# EEG1CH.net
KiCad netlist of a schematic drawn in EAGLE
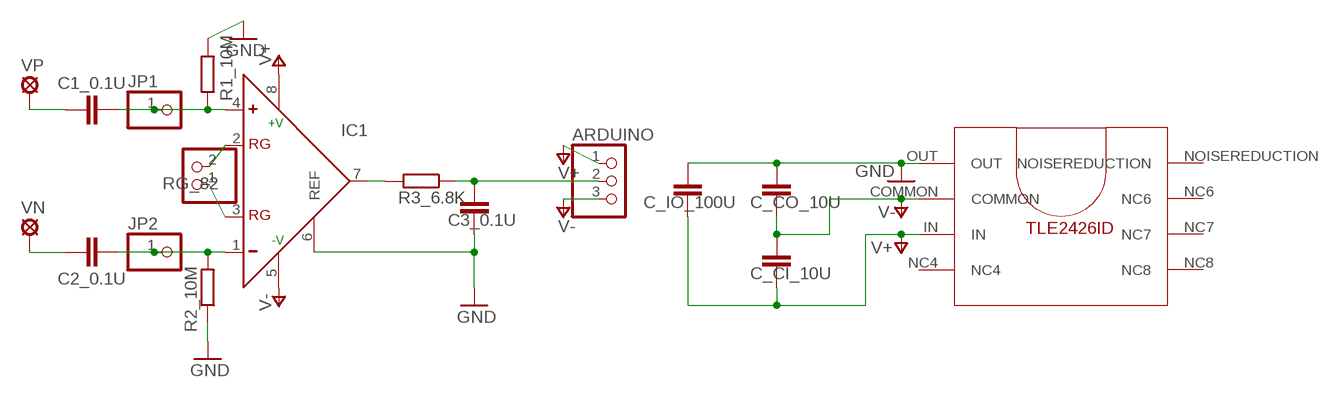
[diagram p0: schematic, sheet 1]

(export (version "E")
  (design (tool "Eeschema 10.0.6"))
  (components
    (comp (ref "ARDUINO")
      (value "PINHD-1X3")
      (footprint "eagle-import:1X03")
      (libsource (lib "eagle-import") (part "PINHD-1X3"))
    )
    (comp (ref "C1_0.1U")
      (value "C2,5-3")
      (footprint "eagle-import:C2.5-3")
      (libsource (lib "eagle-import") (part "C2,5-3"))
    )
    (comp (ref "C2_0.1U")
      (value "C2,5-3")
      (footprint "eagle-import:C2.5-3")
      (libsource (lib "eagle-import") (part "C2,5-3"))
    )
    (comp (ref "C3_0.1U")
      (value "C2,5-3")
      (footprint "eagle-import:C2.5-3")
      (libsource (lib "eagle-import") (part "C2,5-3"))
    )
    (comp (ref "C_CI_10U")
      (value "C2,5-3")
      (footprint "eagle-import:C2.5-3")
      (libsource (lib "eagle-import") (part "C2,5-3"))
    )
    (comp (ref "C_CO_10U")
      (value "C2,5-3")
      (footprint "eagle-import:C2.5-3")
      (libsource (lib "eagle-import") (part "C2,5-3"))
    )
    (comp (ref "C_IO_100U")
      (value "C2,5-3")
      (footprint "eagle-import:C2.5-3")
      (libsource (lib "eagle-import") (part "C2,5-3"))
    )
    (comp (ref "IC1")
      (value "AD8227")
      (footprint "eagle-import:SO8")
      (libsource (lib "eagle-import") (part "AD8227"))
    )
    (comp (ref "JP1")
      (value "PINHD-1X1")
      (footprint "eagle-import:1X01")
      (libsource (lib "eagle-import") (part "PINHD-1X1"))
    )
    (comp (ref "JP2")
      (value "PINHD-1X1")
      (footprint "eagle-import:1X01")
      (libsource (lib "eagle-import") (part "PINHD-1X1"))
    )
    (comp (ref "R1_10M")
      (value "R-EU_R2012")
      (footprint "eagle-import:R2012")
      (libsource (lib "eagle-import") (part "R-EU_R2012"))
    )
    (comp (ref "R2_10M")
      (value "R-EU_R2012")
      (footprint "eagle-import:R2012")
      (libsource (lib "eagle-import") (part "R-EU_R2012"))
    )
    (comp (ref "R3_6.8K")
      (value "R-EU_R2012")
      (footprint "eagle-import:R2012")
      (libsource (lib "eagle-import") (part "R-EU_R2012"))
    )
    (comp (ref "RG_82")
      (value "PINHD-1X2")
      (footprint "eagle-import:1X02")
      (libsource (lib "eagle-import") (part "PINHD-1X2"))
    )
    (comp (ref "U$1")
      (value "TLE2426ID")
      (footprint "eagle-import:TLE2426ID")
      (libsource (lib "eagle-import") (part "TLE2426ID"))
    )
    (comp (ref "VN")
      (value "SE13")
      (footprint "eagle-import:SE13")
      (libsource (lib "eagle-import") (part "SE13"))
    )
    (comp (ref "VP")
      (value "SE13")
      (footprint "eagle-import:SE13")
      (libsource (lib "eagle-import") (part "SE13"))
    )
  )
  (nets
    (net (code "1") (name "GND") (class "Default")
      (node (ref "C3_0.1U") (pin "2") (pinfunction "2_2") (pintype "passive"))
      (node (ref "C_CO_10U") (pin "1") (pinfunction "1_1") (pintype "passive"))
      (node (ref "C_IO_100U") (pin "1") (pinfunction "1_1") (pintype "passive"))
      (node (ref "IC1") (pin "6") (pinfunction "REF_6") (pintype "passive"))
      (node (ref "R1_10M") (pin "2") (pinfunction "2_2") (pintype "passive"))
      (node (ref "R2_10M") (pin "1") (pinfunction "1_1") (pintype "passive"))
      (node (ref "U$1") (pin "OUT") (pinfunction "OUT_OUT") (pintype "bidirectional"))
    )
    (net (code "2") (name "Net-(ARDUINO-Pad2)") (class "Default")
      (node (ref "ARDUINO") (pin "2") (pinfunction "2_2") (pintype "passive"))
      (node (ref "C3_0.1U") (pin "1") (pinfunction "1_1") (pintype "passive"))
      (node (ref "R3_6.8K") (pin "1") (pinfunction "1_1") (pintype "passive"))
    )
    (net (code "3") (name "Net-(C1_0.1U-Pad1)") (class "Default")
      (node (ref "C1_0.1U") (pin "1") (pinfunction "1_1") (pintype "passive"))
      (node (ref "VP") (pin "MP") (pinfunction "MP_MP") (pintype "passive"))
    )
    (net (code "4") (name "Net-(C2_0.1U-Pad1)") (class "Default")
      (node (ref "C2_0.1U") (pin "1") (pinfunction "1_1") (pintype "passive"))
      (node (ref "VN") (pin "MP") (pinfunction "MP_MP") (pintype "passive"))
    )
    (net (code "5") (name "Net-(IC1-+)") (class "Default")
      (node (ref "C1_0.1U") (pin "2") (pinfunction "2_2") (pintype "passive"))
      (node (ref "IC1") (pin "4") (pinfunction "+_4") (pintype "input"))
      (node (ref "JP1") (pin "1") (pinfunction "1_1") (pintype "passive"))
      (node (ref "R1_10M") (pin "1") (pinfunction "1_1") (pintype "passive"))
    )
    (net (code "6") (name "Net-(IC1--)") (class "Default")
      (node (ref "C2_0.1U") (pin "2") (pinfunction "2_2") (pintype "passive"))
      (node (ref "IC1") (pin "1") (pinfunction "-_1") (pintype "input"))
      (node (ref "JP2") (pin "1") (pinfunction "1_1") (pintype "passive"))
      (node (ref "R2_10M") (pin "2") (pinfunction "2_2") (pintype "passive"))
    )
    (net (code "7") (name "Net-(IC1-OUT)") (class "Default")
      (node (ref "IC1") (pin "7") (pinfunction "OUT_7") (pintype "output"))
      (node (ref "R3_6.8K") (pin "2") (pinfunction "2_2") (pintype "passive"))
    )
    (net (code "8") (name "Net-(IC1-RG-Pad2)") (class "Default")
      (node (ref "IC1") (pin "2") (pinfunction "RG_2") (pintype "passive"))
      (node (ref "RG_82") (pin "2") (pinfunction "2_2") (pintype "passive"))
    )
    (net (code "9") (name "Net-(IC1-RG-Pad3)") (class "Default")
      (node (ref "IC1") (pin "3") (pinfunction "RG_3") (pintype "passive"))
      (node (ref "RG_82") (pin "1") (pinfunction "1_1") (pintype "passive"))
    )
    (net (code "10") (name "V+") (class "Default")
      (node (ref "ARDUINO") (pin "1") (pinfunction "1_1") (pintype "passive"))
      (node (ref "C_CI_10U") (pin "2") (pinfunction "2_2") (pintype "passive"))
      (node (ref "C_IO_100U") (pin "2") (pinfunction "2_2") (pintype "passive"))
      (node (ref "IC1") (pin "8") (pinfunction "+V_8") (pintype "power_in"))
      (node (ref "U$1") (pin "IN") (pinfunction "IN_IN") (pintype "bidirectional"))
    )
    (net (code "11") (name "V-") (class "Default")
      (node (ref "ARDUINO") (pin "3") (pinfunction "3_3") (pintype "passive"))
      (node (ref "C_CI_10U") (pin "1") (pinfunction "1_1") (pintype "passive"))
      (node (ref "C_CO_10U") (pin "2") (pinfunction "2_2") (pintype "passive"))
      (node (ref "IC1") (pin "5") (pinfunction "-V_5") (pintype "power_in"))
      (node (ref "U$1") (pin "COMMON") (pinfunction "COMMON_COMMON") (pintype "bidirectional"))
    )
    (net (code "12") (name "unconnected-(U$1-PadNC4)") (class "Default")
      (node (ref "U$1") (pin "NC4") (pinfunction "NC4_NC4") (pintype "bidirectional"))
    )
    (net (code "13") (name "unconnected-(U$1-PadNC6)") (class "Default")
      (node (ref "U$1") (pin "NC6") (pinfunction "NC6_NC6") (pintype "bidirectional"))
    )
    (net (code "14") (name "unconnected-(U$1-PadNC7)") (class "Default")
      (node (ref "U$1") (pin "NC7") (pinfunction "NC7_NC7") (pintype "bidirectional"))
    )
    (net (code "15") (name "unconnected-(U$1-PadNC8)") (class "Default")
      (node (ref "U$1") (pin "NC8") (pinfunction "NC8_NC8") (pintype "bidirectional"))
    )
    (net (code "16") (name "unconnected-(U$1-PadNOISEREDUCTION)") (class "Default")
      (node (ref "U$1") (pin "NOISEREDUCTION") (pinfunction "NOISEREDUCTION_NOISEREDUCTION") (pintype "bidirectional"))
    )
  )
)
